# T1_Power_Top_Level.net
KiCad netlist of a schematic drawn in Altium Designer
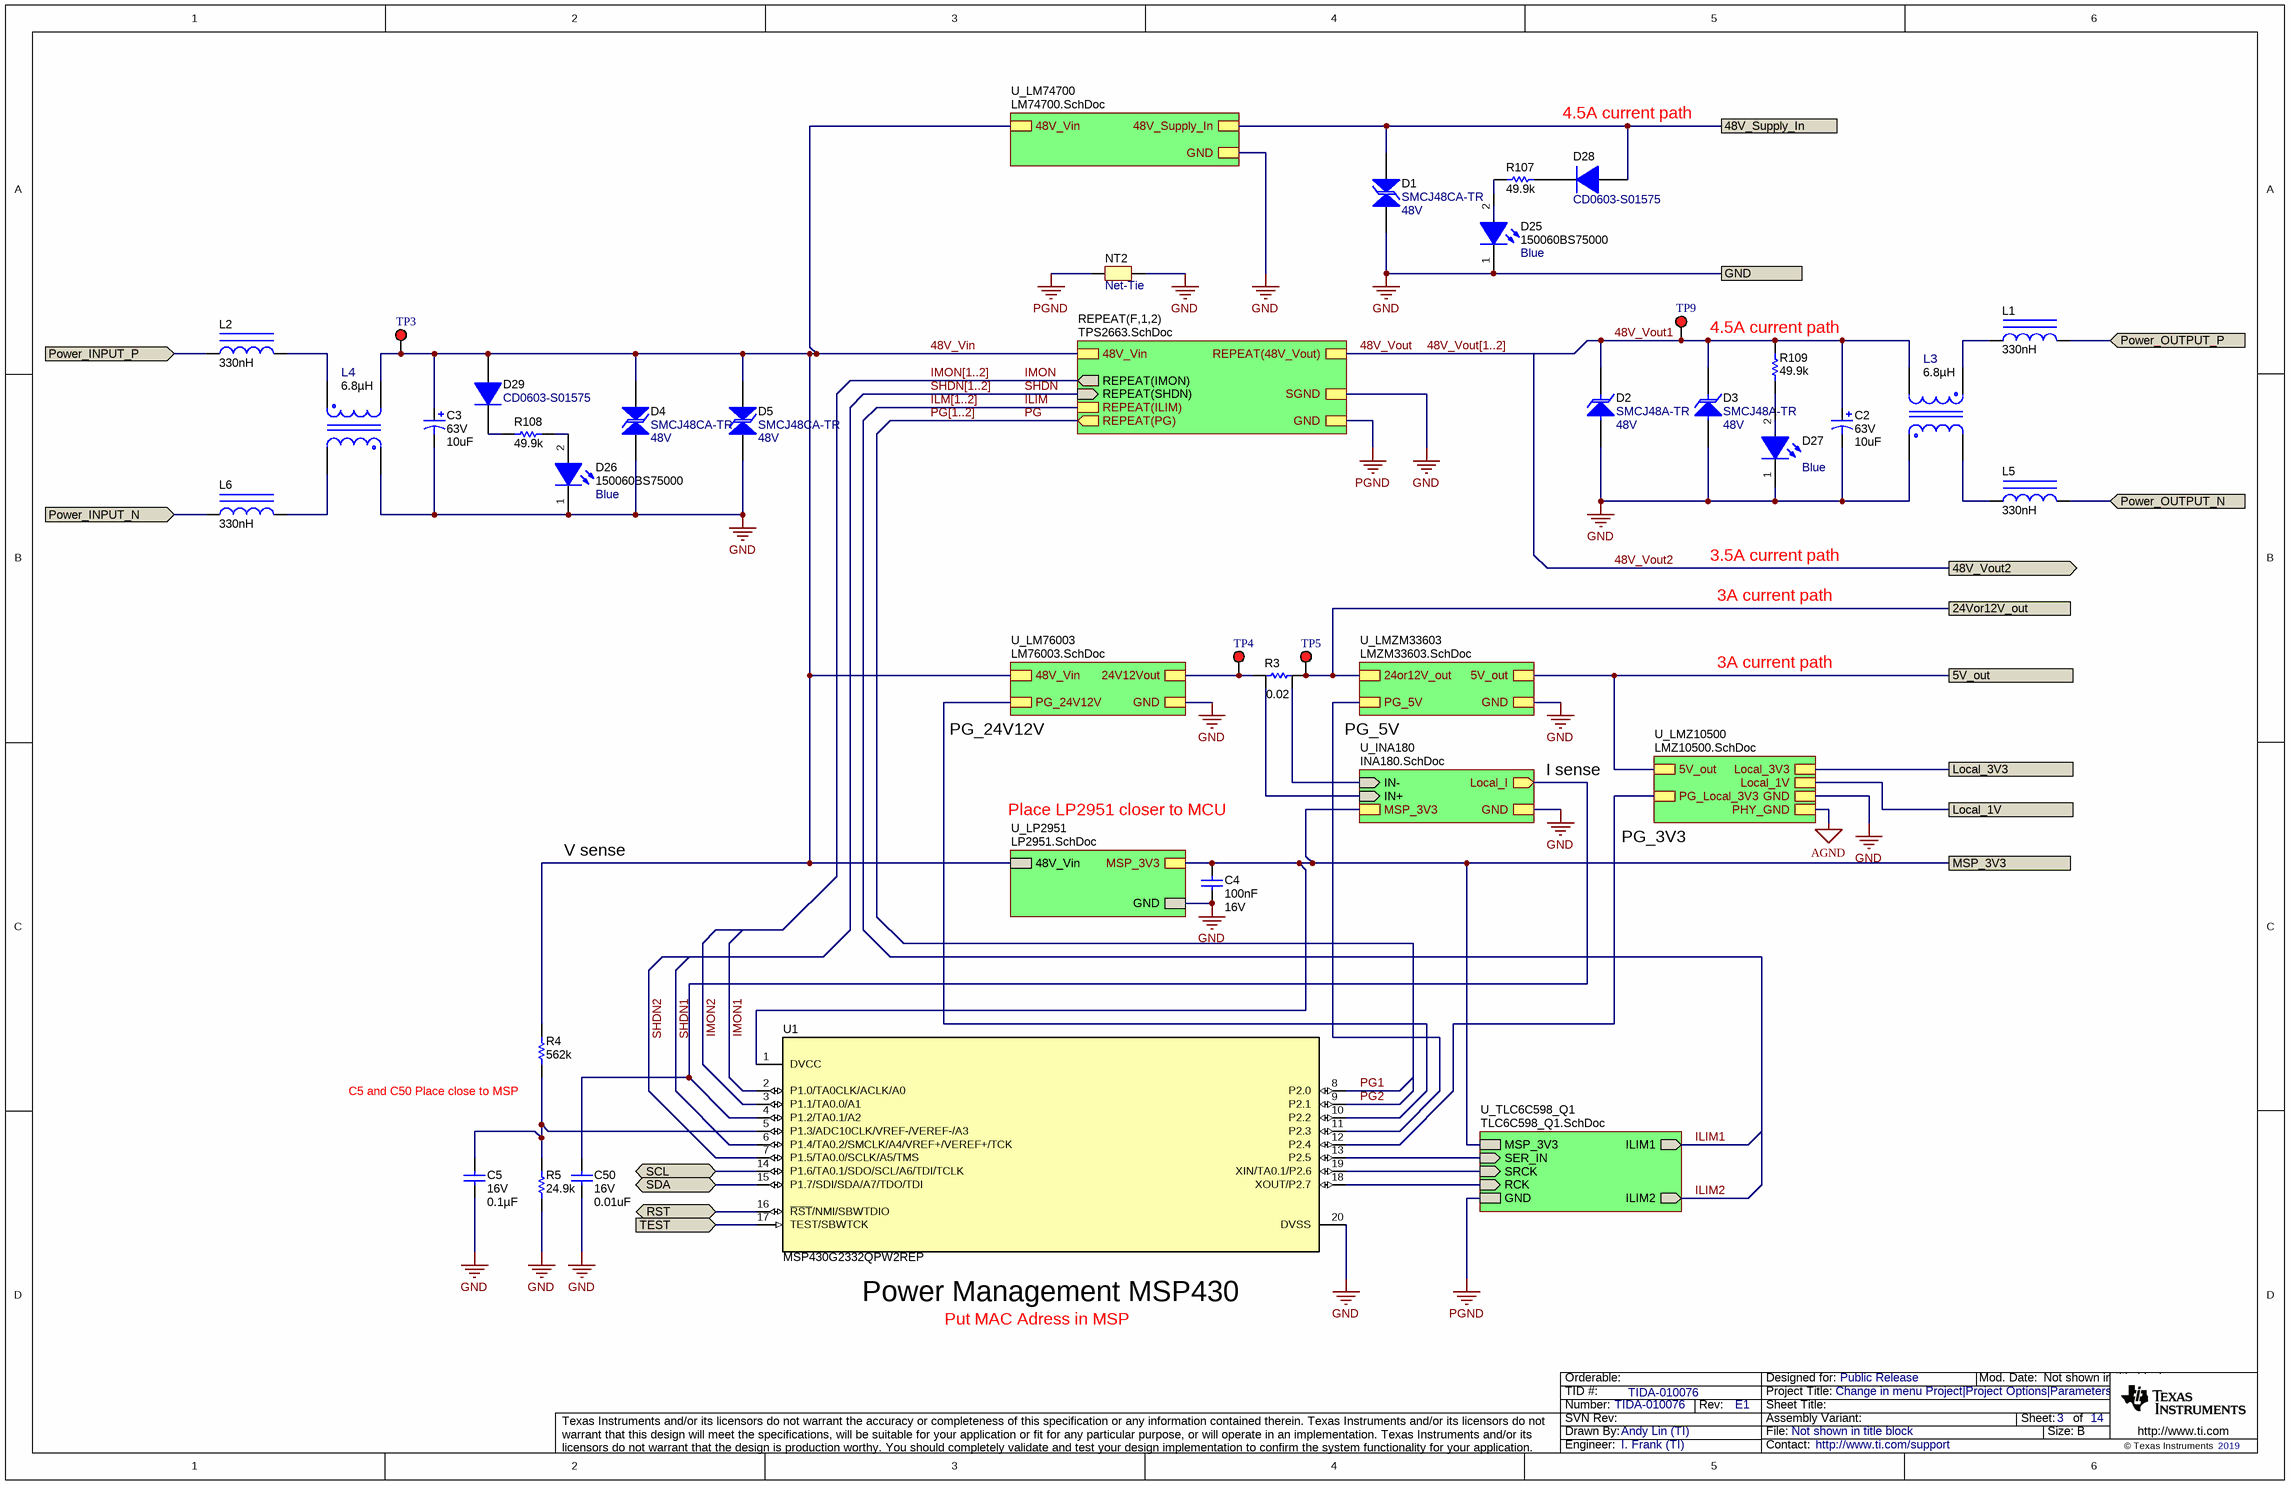
[diagram p0: T1_Power_Top_Level.SchDoc]

(export (version "E")
  (design (tool "Eeschema 10.0.6"))
  (components
    (comp (ref "C2")
      (value "293D106X9063E2TE3")
      (footprint "3216-18")
      (description "CAP, TA, 10 uF, 63 V, +/- 10%, 1 ohm, SMD")
      (fields
        (field (name "MANUFACTURER") "Vishay-Sprague")
        (field (name "VDC_V") "63V")
        (field (name "VALUEDISPLAYED") "10uF")
        (field (name "PUBLISHER") "Texas Instruments")
      )
      (libsource (lib "Altium Vault - TI") (part "Cap_Polarized"))
    )
    (comp (ref "C3")
      (value "293D106X9063E2TE3")
      (footprint "3216-18")
      (description "CAP, TA, 10 uF, 63 V, +/- 10%, 1 ohm, SMD")
      (fields
        (field (name "MANUFACTURER") "Vishay-Sprague")
        (field (name "VDC_V") "63V")
        (field (name "VALUEDISPLAYED") "10uF")
        (field (name "PUBLISHER") "Texas Instruments")
      )
      (libsource (lib "Altium Vault - TI") (part "Cap_Polarized"))
    )
    (comp (ref "C4")
      (value "GRM188R71C104KA01D")
      (footprint "0603")
      (description "CAP, CERM, 0.1 uF, 16 V, +/- 10%, X7R, 0603")
      (fields
        (field (name "MANUFACTURER") "MuRata")
        (field (name "CAP_F") "100nF")
        (field (name "VDC_V") "16V")
        (field (name "PUBLISHER") "Texas Instruments")
      )
      (libsource (lib "Altium Vault - TI") (part "Capacitor"))
    )
    (comp (ref "C5")
      (value "GCM155R71C104JA55D")
      (footprint "0402")
      (description "CAP, CERM, 0.1 µF, 16 V,+/- 5%, X7R, AEC-Q200 Grade 1, 0402")
      (fields
        (field (name "MANUFACTURER") "MuRata")
        (field (name "VDC_V") "16V")
        (field (name "VALUEDISPLAYED") "0.1µF")
      )
      (libsource (lib "Altium Vault - TI") (part "Capacitor"))
    )
    (comp (ref "C50")
      (value "GRM155R71C103KA01D")
      (footprint "0402")
      (description "CAP, CERM, 0.01 uF, 16 V, +/- 10%, X7R, 0402")
      (fields
        (field (name "MANUFACTURER") "MuRata")
        (field (name "VDC_V") "16V")
        (field (name "VALUEDISPLAYED") "0.01uF")
        (field (name "PUBLISHER") "Texas Instruments")
      )
      (libsource (lib "Altium Vault - TI") (part "Capacitor"))
    )
    (comp (ref "D1")
      (value "SMCJ48CA-TR")
      (footprint "SMC_Bi")
      (description "Diode, TVS, Bi, 48 V, 77.4 Vc, 1500 W, 20 A, SMC (No Polarity Mark)")
      (fields (field (name "ALTIUM_VALUE") "48V") (field (name "MANUFACTURER") "STMicroelectronics"))
      (libsource (lib "Altium Vault - TI") (part "Diode_TVS_Bi"))
    )
    (comp (ref "D2")
      (value "SMCJ48A-TR")
      (footprint "SMC")
      (description "Diode, TVS, Uni, 48 V, 77.4 Vc, 1500 W, 20 A, SMC")
      (fields (field (name "ALTIUM_VALUE") "48V") (field (name "MANUFACTURER") "STMicroelectronics"))
      (libsource (lib "Altium Vault - TI") (part "Diode_TVS_Uni"))
    )
    (comp (ref "D3")
      (value "SMCJ48A-TR")
      (footprint "SMC")
      (description "Diode, TVS, Uni, 48 V, 77.4 Vc, 1500 W, 20 A, SMC")
      (fields (field (name "ALTIUM_VALUE") "48V") (field (name "MANUFACTURER") "STMicroelectronics"))
      (libsource (lib "Altium Vault - TI") (part "Diode_TVS_Uni"))
    )
    (comp (ref "D4")
      (value "SMCJ48CA-TR")
      (footprint "SMC_Bi")
      (description "Diode, TVS, Bi, 48 V, 77.4 Vc, 1500 W, 20 A, SMC (No Polarity Mark)")
      (fields (field (name "ALTIUM_VALUE") "48V") (field (name "MANUFACTURER") "STMicroelectronics"))
      (libsource (lib "Altium Vault - TI") (part "Diode_TVS_Bi"))
    )
    (comp (ref "D5")
      (value "SMCJ48CA-TR")
      (footprint "SMC_Bi")
      (description "Diode, TVS, Bi, 48 V, 77.4 Vc, 1500 W, 20 A, SMC (No Polarity Mark)")
      (fields (field (name "ALTIUM_VALUE") "48V") (field (name "MANUFACTURER") "STMicroelectronics"))
      (libsource (lib "Altium Vault - TI") (part "Diode_TVS_Bi"))
    )
    (comp (ref "D25")
      (value "150060BS75000")
      (footprint "WL-SMCW_Blue")
      (description "LED, Blue, SMD")
      (fields (field (name "ALTIUM_VALUE") "Blue") (field (name "MANUFACTURER") "Wurth Elektronik"))
      (libsource (lib "Altium Vault - TI") (part "LED_A2_K1"))
    )
    (comp (ref "D26")
      (value "150060BS75000")
      (footprint "WL-SMCW_Blue")
      (description "LED, Blue, SMD")
      (fields (field (name "ALTIUM_VALUE") "Blue") (field (name "MANUFACTURER") "Wurth Elektronik"))
      (libsource (lib "Altium Vault - TI") (part "LED_A2_K1"))
    )
    (comp (ref "D27")
      (value "Blue")
      (footprint "WL-SMCW_Blue")
      (description "LED, Blue, SMD")
      (fields (field (name "MANUFACTURER") "Wurth Elektronik") (field (name "PARTNUMBER") "150060BS75000"))
      (libsource (lib "Altium Vault - TI") (part "LED_A2_K1"))
    )
    (comp (ref "D28")
      (value "CD0603-S01575")
      (footprint "Diode_0603")
      (description "Diode, Switching, 100 V, 0.15 A, 0603 Diode")
      (fields (field (name "MANUFACTURER") "Bourns"))
      (libsource (lib "Altium Vault - TI") (part "DIODE"))
    )
    (comp (ref "D29")
      (value "CD0603-S01575")
      (footprint "Diode_0603")
      (description "Diode, Switching, 100 V, 0.15 A, 0603 Diode")
      (fields (field (name "MANUFACTURER") "Bourns"))
      (libsource (lib "Altium Vault - TI") (part "DIODE"))
    )
    (comp (ref "L1")
      (value "744383360033")
      (footprint "WE-MAPI_3020")
      (description "Inductor, 330 nH, 5.5 A, 0.014 ohm, SMD")
      (fields
        (field (name "MANUFACTURER") "Wurth Elektronik")
        (field (name "VALUEDISPLAYED") "330nH")
        (field (name "PUBLISHER") "Texas Instruments")
      )
      (libsource (lib "Altium Vault - TI") (part "Inductor_Iron"))
    )
    (comp (ref "L2")
      (value "744383360033")
      (footprint "WE-MAPI_3020")
      (description "Inductor, 330 nH, 5.5 A, 0.014 ohm, SMD")
      (fields
        (field (name "MANUFACTURER") "Wurth Elektronik")
        (field (name "VALUEDISPLAYED") "330nH")
        (field (name "PUBLISHER") "Texas Instruments")
      )
      (libsource (lib "Altium Vault - TI") (part "Inductor_Iron"))
    )
    (comp (ref "L3")
      (value "7448991068")
      (footprint "FP-7448991068_SMT_10MM0_10MM0-MFG")
      (fields (field (name "MANUFACTURER") "Wurth Electronics") (field (name "IND_H") "6.8µH"))
      (libsource (lib "") (part "SYM-7448991068_1"))
    )
    (comp (ref "L4")
      (value "7448991068")
      (footprint "FP-7448991068_SMT_10MM0_10MM0-MFG")
      (fields (field (name "MANUFACTURER") "Wurth Electronics") (field (name "IND_H") "6.8µH"))
      (libsource (lib "Altium Vault - TI") (part "SYM-7448991068"))
    )
    (comp (ref "L5")
      (value "744383360033")
      (footprint "WE-MAPI_3020")
      (description "Inductor, 330 nH, 5.5 A, 0.014 ohm, SMD")
      (fields
        (field (name "MANUFACTURER") "Wurth Elektronik")
        (field (name "VALUEDISPLAYED") "330nH")
        (field (name "PUBLISHER") "Texas Instruments")
      )
      (libsource (lib "Altium Vault - TI") (part "Inductor_Iron"))
    )
    (comp (ref "L6")
      (value "744383360033")
      (footprint "WE-MAPI_3020")
      (description "Inductor, 330 nH, 5.5 A, 0.014 ohm, SMD")
      (fields
        (field (name "MANUFACTURER") "Wurth Elektronik")
        (field (name "VALUEDISPLAYED") "330nH")
        (field (name "PUBLISHER") "Texas Instruments")
      )
      (libsource (lib "Altium Vault - TI") (part "Inductor_Iron"))
    )
    (comp (ref "NT2")
      (value "Net-Tie")
      (footprint "NetTie_0402")
      (description "Single point connection between nets.")
      (libsource (lib "Altium Vault - TI") (part "Net-Tie"))
    )
    (comp (ref "R3")
      (value "LVK12R020FER")
      (footprint "LVK12")
      (description "RES, 0.02, 1%, 0.5 W, 1206 sense")
      (fields
        (field (name "MANUFACTURER") "Ohmite")
        (field (name "VALUEDISPLAYED") "0.02")
        (field (name "PUBLISHER") "Texas Instruments")
      )
      (libsource (lib "Altium Vault - TI") (part "Resistor_Kelvin"))
    )
    (comp (ref "R4")
      (value "CRCW0402562KFKED")
      (footprint "0402")
      (description "RES, 562 k, 1%, 0.063 W, AEC-Q200 Grade 0, 0402")
      (fields (field (name "MANUFACTURER") "Vishay-Dale") (field (name "VALUEDISPLAYED") "562k"))
      (libsource (lib "Altium Vault - TI") (part "Resistor"))
    )
    (comp (ref "R5")
      (value "CRCW040224K9FKED")
      (footprint "0402")
      (description "RES, 24.9 k, 1%, 0.063 W, AEC-Q200 Grade 0, 0402")
      (fields (field (name "MANUFACTURER") "Vishay-Dale") (field (name "VALUEDISPLAYED") "24.9k"))
      (libsource (lib "Altium Vault - TI") (part "Resistor"))
    )
    (comp (ref "R107")
      (value "CRCW060349K9FKEA")
      (footprint "0603")
      (description "RES, 49.9 k, 1%, 0.1 W, 0603")
      (fields
        (field (name "MANUFACTURER") "Vishay-Dale")
        (field (name "VALUEDISPLAYED") "49.9k")
        (field (name "PUBLISHER") "Texas Instruments")
      )
      (libsource (lib "Altium Vault - TI") (part "Resistor"))
    )
    (comp (ref "R108")
      (value "CRCW060349K9FKEA")
      (footprint "0603")
      (description "RES, 49.9 k, 1%, 0.1 W, 0603")
      (fields
        (field (name "MANUFACTURER") "Vishay-Dale")
        (field (name "VALUEDISPLAYED") "49.9k")
        (field (name "PUBLISHER") "Texas Instruments")
      )
      (libsource (lib "Altium Vault - TI") (part "Resistor"))
    )
    (comp (ref "R109")
      (value "CRCW060349K9FKEA")
      (footprint "0603")
      (description "RES, 49.9 k, 1%, 0.1 W, 0603")
      (fields
        (field (name "MANUFACTURER") "Vishay-Dale")
        (field (name "VALUEDISPLAYED") "49.9k")
        (field (name "PUBLISHER") "Texas Instruments")
      )
      (libsource (lib "Altium Vault - TI") (part "Resistor"))
    )
    (comp (ref "TP3")
      (value "5000")
      (footprint "Keystone5000")
      (description "Test Point, Miniature, Red, TH")
      (fields (field (name "MANUFACTURER") "Keystone") (field (name "PUBLISHER") "Texas Instruments"))
      (libsource (lib "Altium Vault - TI") (part "5000"))
    )
    (comp (ref "TP4")
      (value "5000")
      (footprint "Keystone5000")
      (description "Test Point, Miniature, Red, TH")
      (fields (field (name "MANUFACTURER") "Keystone") (field (name "PUBLISHER") "Texas Instruments"))
      (libsource (lib "Altium Vault - TI") (part "5000"))
    )
    (comp (ref "TP5")
      (value "5000")
      (footprint "Keystone5000")
      (description "Test Point, Miniature, Red, TH")
      (fields (field (name "MANUFACTURER") "Keystone") (field (name "PUBLISHER") "Texas Instruments"))
      (libsource (lib "Altium Vault - TI") (part "5000"))
    )
    (comp (ref "TP9")
      (value "5000")
      (footprint "Keystone5000")
      (description "Test Point, Miniature, Red, TH")
      (fields (field (name "MANUFACTURER") "Keystone") (field (name "PUBLISHER") "Texas Instruments"))
      (libsource (lib "Altium Vault - TI") (part "5000"))
    )
    (comp (ref "U1")
      (value "MSP430G2332QPW2REP")
      (footprint "PW0020A_L")
      (description "Enhanced Product Mixed Signal Microcontroller, PW0020A (TSSOP-20)")
      (fields
        (field (name "PARTNUMBER") "MSP430G2332QPW2REP")
        (field (name "MANUFACTURER") "Texas Instruments")
        (field (name "ALTERNATE PARTNUMBER") "MSP430G2332QPW2EP")
        (field (name "PUBLISHER") "Texas Instruments")
      )
      (libsource (lib "Altium Vault - TI") (part "MSP430G2332"))
    )
  )
  (nets
    (net (code "4") (name "/24V12Vout") (class "Default")
      (node (ref "R3") (pin "2") (pinfunction "2_2") (pintype "passive"))
      (node (ref "TP4") (pin "1") (pintype "passive"))
    )
    (net (code "5") (name "/24Vor12V_out") (class "Default")
      (node (ref "R3") (pin "1") (pinfunction "1_1") (pintype "passive"))
      (node (ref "TP5") (pin "1") (pintype "passive"))
    )
    (net (code "6") (name "/48V_Supply_In") (class "Default")
      (node (ref "D1") (pin "2") (pinfunction "2_2") (pintype "passive"))
      (node (ref "D28") (pin "2") (pinfunction "A_2") (pintype "passive"))
    )
    (net (code "7") (name "/48V_Vin") (class "Default")
      (node (ref "C3") (pin "1") (pinfunction "+_1") (pintype "passive"))
      (node (ref "D29") (pin "2") (pinfunction "A_2") (pintype "passive"))
      (node (ref "D4") (pin "2") (pinfunction "2_2") (pintype "passive"))
      (node (ref "D5") (pin "2") (pinfunction "2_2") (pintype "passive"))
      (node (ref "L4") (pin "2") (pinfunction "2_2") (pintype "passive"))
      (node (ref "R4") (pin "2") (pinfunction "2_2") (pintype "passive"))
      (node (ref "TP3") (pin "1") (pintype "passive"))
    )
    (net (code "9") (name "/48V_Vout1") (class "Default")
      (node (ref "C2") (pin "1") (pinfunction "+_1") (pintype "passive"))
      (node (ref "D2") (pin "1") (pinfunction "K_1") (pintype "passive"))
      (node (ref "D3") (pin "1") (pinfunction "K_1") (pintype "passive"))
      (node (ref "L3") (pin "4") (pinfunction "4_4") (pintype "passive"))
      (node (ref "R109") (pin "2") (pinfunction "2_2") (pintype "passive"))
      (node (ref "TP9") (pin "1") (pintype "passive"))
    )
    (net (code "17") (name "/IMON1") (class "Default")
      (node (ref "U1") (pin "2") (pinfunction "P1.0/TA0CLK/ACLK/A0_2") (pintype "bidirectional"))
    )
    (net (code "18") (name "/IMON2") (class "Default")
      (node (ref "U1") (pin "3") (pinfunction "P1.1/TA0.0/A1_3") (pintype "bidirectional"))
    )
    (net (code "20") (name "/IN+") (class "Default")
      (node (ref "R3") (pin "4") (pinfunction "4_4") (pintype "passive"))
    )
    (net (code "21") (name "/IN-") (class "Default")
      (node (ref "R3") (pin "3") (pinfunction "3_3") (pintype "passive"))
    )
    (net (code "24") (name "/Local_I") (class "Default")
      (node (ref "C50") (pin "1") (pinfunction "1_1") (pintype "passive"))
      (node (ref "U1") (pin "4") (pinfunction "P1.2/TA0.1/A2_4") (pintype "bidirectional"))
    )
    (net (code "25") (name "/MSP_3V3") (class "Default")
      (node (ref "C4") (pin "1") (pinfunction "1_1") (pintype "passive"))
      (node (ref "U1") (pin "1") (pinfunction "DVCC_1") (pintype "power_in"))
    )
    (net (code "27") (name "/PG1") (class "Default")
      (node (ref "U1") (pin "8") (pinfunction "P2.0_8") (pintype "bidirectional"))
    )
    (net (code "28") (name "/PG2") (class "Default")
      (node (ref "U1") (pin "9") (pinfunction "P2.1_9") (pintype "bidirectional"))
    )
    (net (code "30") (name "/PG_5V") (class "Default")
      (node (ref "U1") (pin "11") (pinfunction "P2.3_11") (pintype "bidirectional"))
    )
    (net (code "31") (name "/PG_24V12V") (class "Default")
      (node (ref "U1") (pin "10") (pinfunction "P2.2_10") (pintype "bidirectional"))
    )
    (net (code "32") (name "/PG_Local_3V3") (class "Default")
      (node (ref "U1") (pin "12") (pinfunction "P2.4_12") (pintype "bidirectional"))
    )
    (net (code "33") (name "/Power_INPUT_N") (class "Default")
      (node (ref "L6") (pin "1") (pinfunction "1_1") (pintype "passive"))
    )
    (net (code "34") (name "/Power_INPUT_P") (class "Default")
      (node (ref "L2") (pin "1") (pinfunction "1_1") (pintype "passive"))
    )
    (net (code "35") (name "/Power_OUTPUT_N") (class "Default")
      (node (ref "L5") (pin "2") (pinfunction "2_2") (pintype "passive"))
    )
    (net (code "36") (name "/Power_OUTPUT_P") (class "Default")
      (node (ref "L1") (pin "2") (pinfunction "2_2") (pintype "passive"))
    )
    (net (code "37") (name "/RCK") (class "Default")
      (node (ref "U1") (pin "18") (pinfunction "XOUT/P2.7_18") (pintype "bidirectional"))
    )
    (net (code "38") (name "/RST") (class "Default")
      (node (ref "U1") (pin "16") (pinfunction "~{RST}/NMI/SBWTDIO_16") (pintype "bidirectional"))
    )
    (net (code "39") (name "/SCL") (class "Default")
      (node (ref "U1") (pin "14") (pinfunction "P1.6/TA0.1/SDO/SCL/A6/TDI/TCLK_14") (pintype "bidirectional"))
    )
    (net (code "40") (name "/SDA") (class "Default")
      (node (ref "U1") (pin "15") (pinfunction "P1.7/SDI/SDA/A7/TDO/TDI_15") (pintype "bidirectional"))
    )
    (net (code "41") (name "/SER_IN") (class "Default")
      (node (ref "U1") (pin "13") (pinfunction "P2.5_13") (pintype "bidirectional"))
    )
    (net (code "43") (name "/SHDN1") (class "Default")
      (node (ref "U1") (pin "6") (pinfunction "P1.4/TA0.2/SMCLK/A4/VREF+/VEREF+/TCK_6") (pintype "bidirectional"))
    )
    (net (code "44") (name "/SHDN2") (class "Default")
      (node (ref "U1") (pin "7") (pinfunction "P1.5/TA0.0/SCLK/A5/TMS_7") (pintype "bidirectional"))
    )
    (net (code "46") (name "/SRCK") (class "Default")
      (node (ref "U1") (pin "19") (pinfunction "XIN/TA0.1/P2.6_19") (pintype "bidirectional"))
    )
    (net (code "47") (name "/TEST") (class "Default")
      (node (ref "U1") (pin "17") (pinfunction "TEST/SBWTCK_17") (pintype "input"))
    )
    (net (code "49") (name "GND") (class "Default")
      (node (ref "C2") (pin "2") (pinfunction "-_2") (pintype "passive"))
      (node (ref "C3") (pin "2") (pinfunction "-_2") (pintype "passive"))
      (node (ref "C4") (pin "2") (pinfunction "2_2") (pintype "passive"))
      (node (ref "C5") (pin "2") (pinfunction "2_2") (pintype "passive"))
      (node (ref "C50") (pin "2") (pinfunction "2_2") (pintype "passive"))
      (node (ref "D1") (pin "1") (pinfunction "1_1") (pintype "passive"))
      (node (ref "D2") (pin "2") (pinfunction "A_2") (pintype "passive"))
      (node (ref "D25") (pin "1") (pinfunction "K_1") (pintype "passive"))
      (node (ref "D26") (pin "1") (pinfunction "K_1") (pintype "passive"))
      (node (ref "D27") (pin "1") (pinfunction "K_1") (pintype "passive"))
      (node (ref "D3") (pin "2") (pinfunction "A_2") (pintype "passive"))
      (node (ref "D4") (pin "1") (pinfunction "1_1") (pintype "passive"))
      (node (ref "D5") (pin "1") (pinfunction "1_1") (pintype "passive"))
      (node (ref "L3") (pin "1") (pinfunction "1_1") (pintype "passive"))
      (node (ref "L4") (pin "3") (pinfunction "3_3") (pintype "passive"))
      (node (ref "NT2") (pin "2") (pinfunction "2_2") (pintype "passive"))
      (node (ref "R5") (pin "1") (pinfunction "1_1") (pintype "passive"))
      (node (ref "U1") (pin "20") (pinfunction "DVSS_20") (pintype "power_in"))
    )
    (net (code "50") (name "Net-(D25-A)") (class "Default")
      (node (ref "D25") (pin "2") (pinfunction "A_2") (pintype "passive"))
      (node (ref "R107") (pin "2") (pinfunction "2_2") (pintype "passive"))
    )
    (net (code "51") (name "Net-(D26-A)") (class "Default")
      (node (ref "D26") (pin "2") (pinfunction "A_2") (pintype "passive"))
      (node (ref "R108") (pin "1") (pinfunction "1_1") (pintype "passive"))
    )
    (net (code "52") (name "Net-(D27-A)") (class "Default")
      (node (ref "D27") (pin "2") (pinfunction "A_2") (pintype "passive"))
      (node (ref "R109") (pin "1") (pinfunction "1_1") (pintype "passive"))
    )
    (net (code "53") (name "Net-(D28-K)") (class "Default")
      (node (ref "D28") (pin "1") (pinfunction "K_1") (pintype "passive"))
      (node (ref "R107") (pin "1") (pinfunction "1_1") (pintype "passive"))
    )
    (net (code "54") (name "Net-(D29-K)") (class "Default")
      (node (ref "D29") (pin "1") (pinfunction "K_1") (pintype "passive"))
      (node (ref "R108") (pin "2") (pinfunction "2_2") (pintype "passive"))
    )
    (net (code "55") (name "Net-(L1-Pad1)") (class "Default")
      (node (ref "L1") (pin "1") (pinfunction "1_1") (pintype "passive"))
      (node (ref "L3") (pin "3") (pinfunction "3_3") (pintype "passive"))
    )
    (net (code "56") (name "Net-(L2-Pad2)") (class "Default")
      (node (ref "L2") (pin "2") (pinfunction "2_2") (pintype "passive"))
      (node (ref "L4") (pin "1") (pinfunction "1_1") (pintype "passive"))
    )
    (net (code "57") (name "Net-(L3-Pad2)") (class "Default")
      (node (ref "L3") (pin "2") (pinfunction "2_2") (pintype "passive"))
      (node (ref "L5") (pin "1") (pinfunction "1_1") (pintype "passive"))
    )
    (net (code "58") (name "Net-(L4-Pad4)") (class "Default")
      (node (ref "L4") (pin "4") (pinfunction "4_4") (pintype "passive"))
      (node (ref "L6") (pin "2") (pinfunction "2_2") (pintype "passive"))
    )
    (net (code "59") (name "Net-(U1-P1.3{slash}ADC10CLK{slash}VREF-{slash}VEREF-{slash}A3)") (class "Default")
      (node (ref "C5") (pin "1") (pinfunction "1_1") (pintype "passive"))
      (node (ref "R4") (pin "1") (pinfunction "1_1") (pintype "passive"))
      (node (ref "R5") (pin "2") (pinfunction "2_2") (pintype "passive"))
      (node (ref "U1") (pin "5") (pinfunction "P1.3/ADC10CLK/VREF-/VEREF-/A3_5") (pintype "bidirectional"))
    )
    (net (code "60") (name "PGND") (class "Default")
      (node (ref "NT2") (pin "1") (pinfunction "1_1") (pintype "passive"))
    )
  )
)
